# SCH_pogo-adapter-v4_2024-10-28.net
KiCad netlist of a schematic drawn in EasyEDA
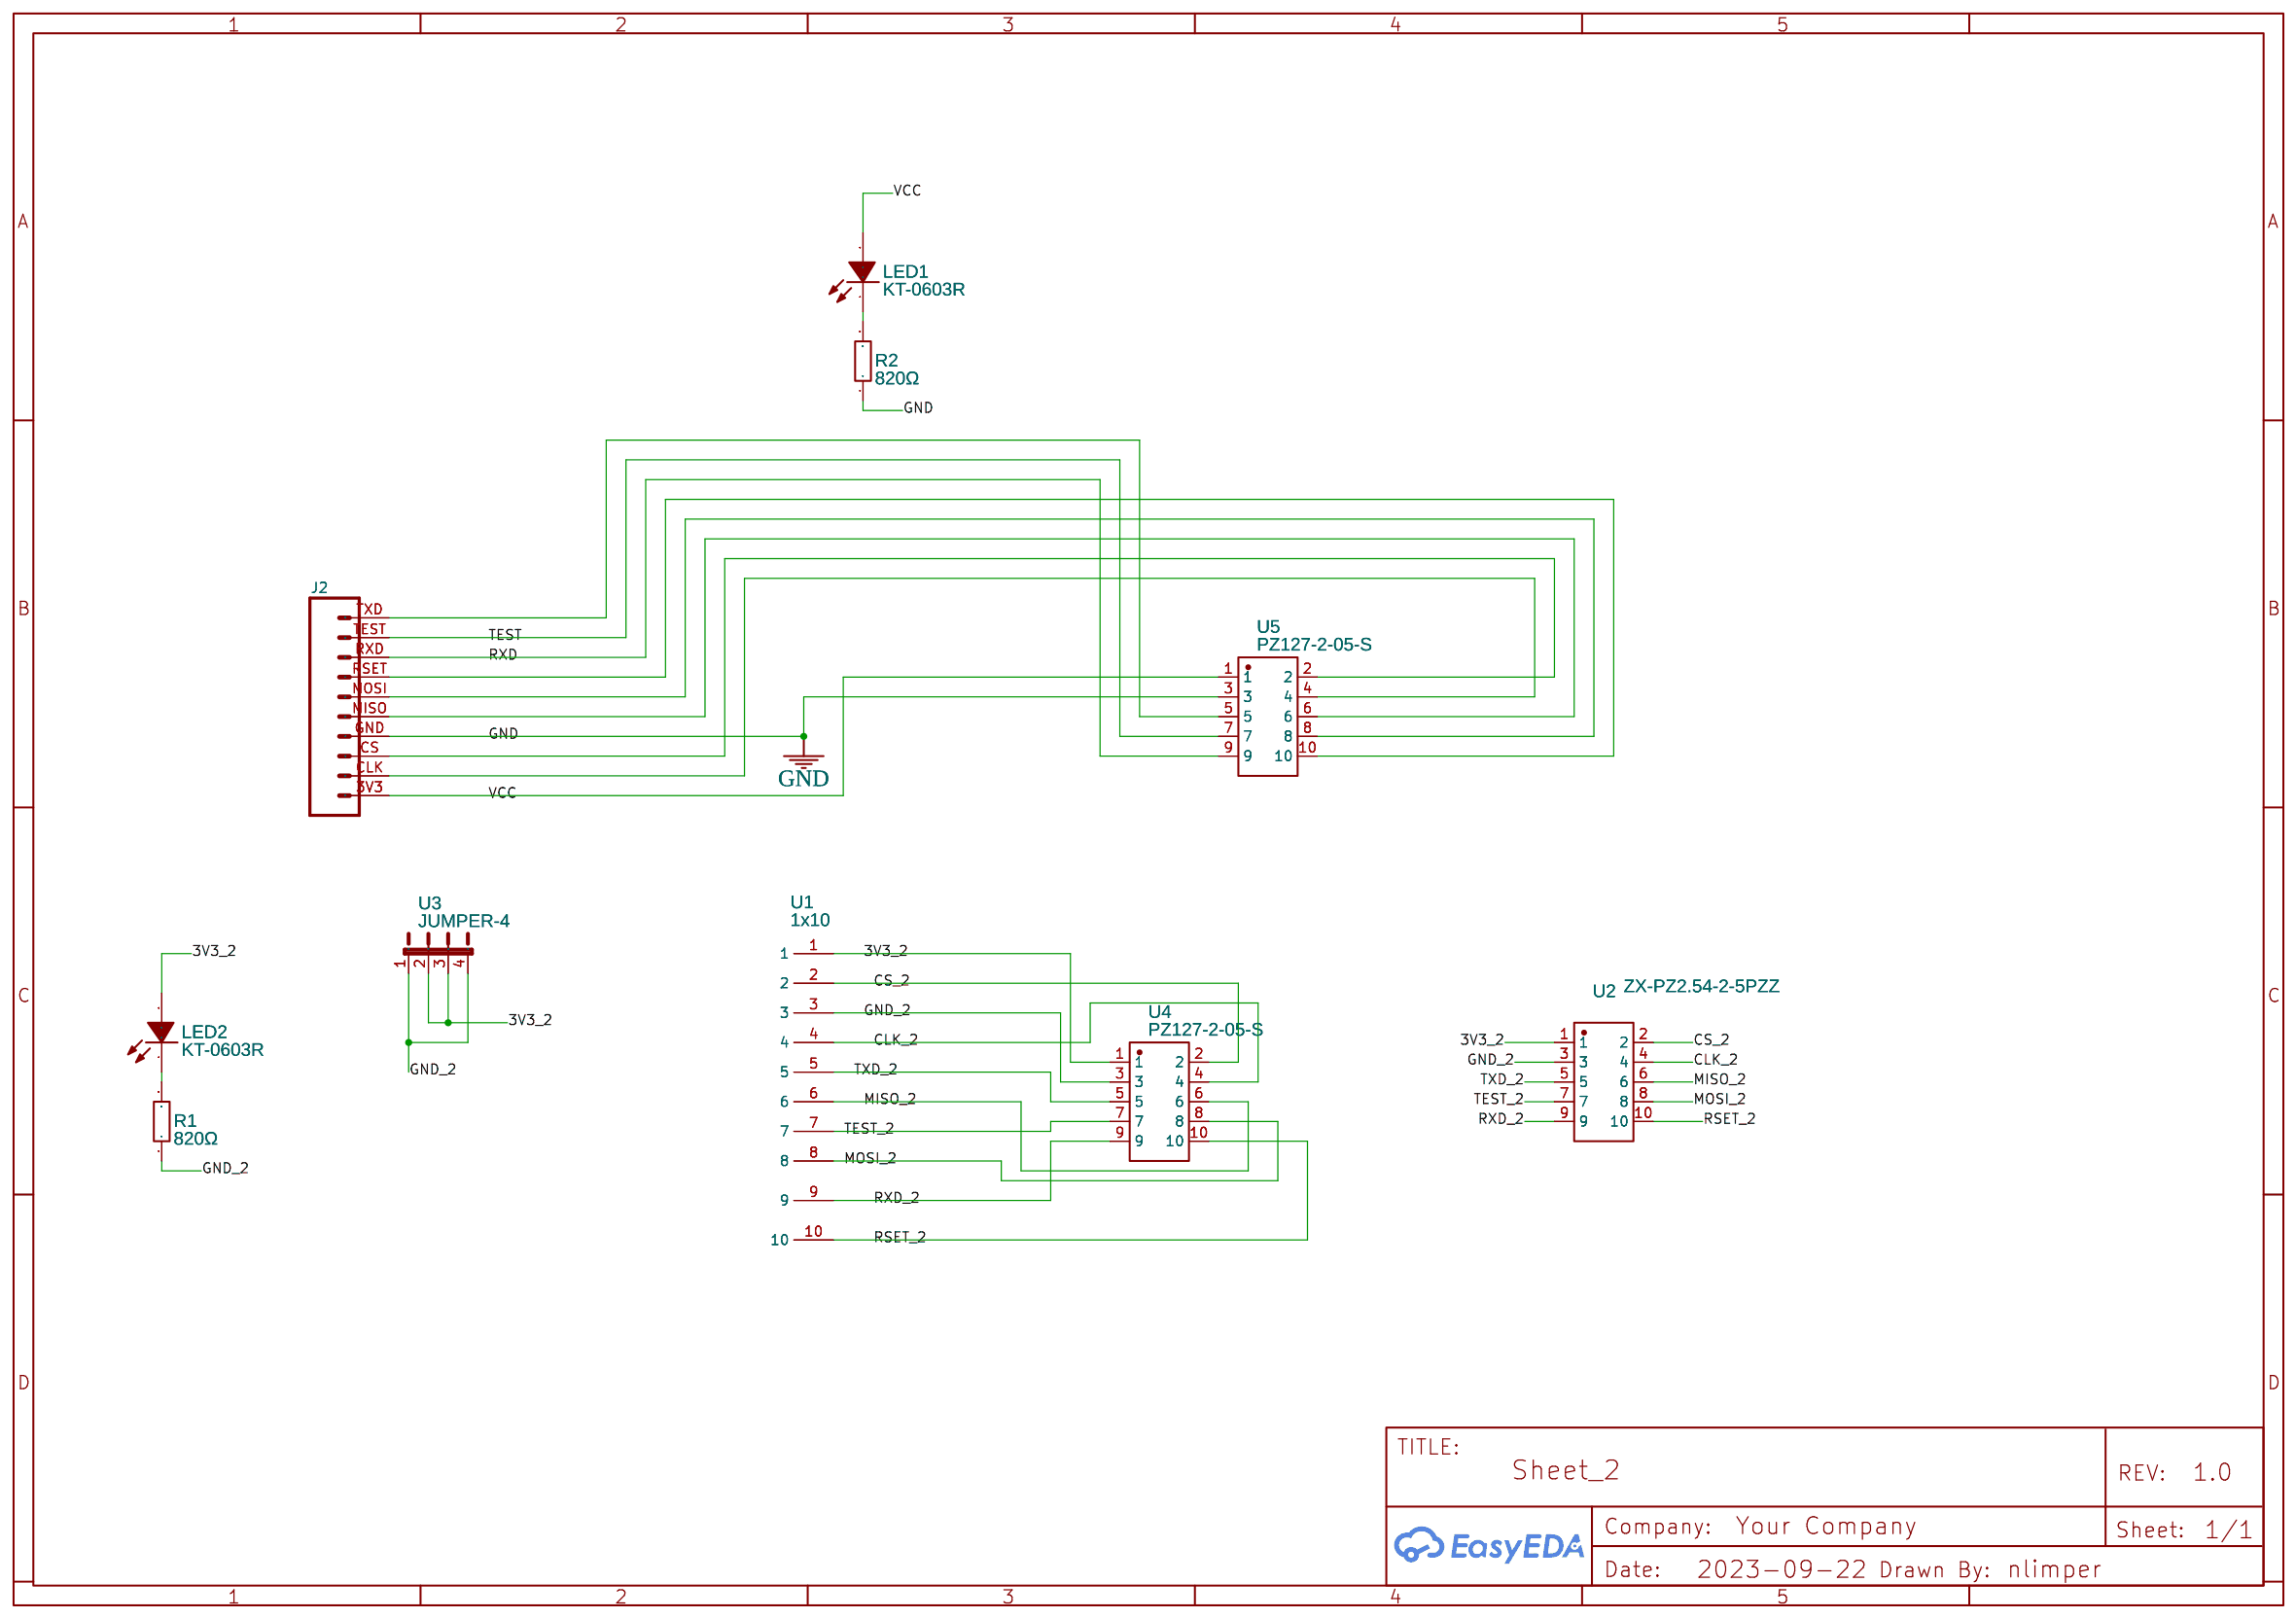
[diagram p0: schematic sheet]

(export (version "E")
  (design (tool "Eeschema 10.0.6"))
  (components
    (comp (ref "J2") (value "SOLUM_ZBS_DEBUG") (libsource (lib "") (part "Unknown_150_-480")))
    (comp (ref "LED1")
      (value "KT-0603R")
      (fields (field (name "Manufacturer") "KENTO"))
      (libsource (lib "") (part "KT-0603R"))
    )
    (comp (ref "LED2")
      (value "KT-0603R")
      (fields (field (name "Manufacturer") "KENTO"))
      (libsource (lib "") (part "KT-0603R"))
    )
    (comp (ref "R1")
      (value "820Ω")
      (fields
        (field (name "Manufacturer Part") "0402WGF8200TCE")
        (field (name "Manufacturer") "UNI-ROYAL(厚声)")
      )
      (libsource (lib "") (part "0402WGF8200TCE"))
    )
    (comp (ref "R2")
      (value "820Ω")
      (fields
        (field (name "Manufacturer Part") "0402WGF8200TCE")
        (field (name "Manufacturer") "UNI-ROYAL(厚声)")
      )
      (libsource (lib "") (part "0402WGF8200TCE"))
    )
    (comp (ref "U1") (value "1x10") (libsource (lib "") (part "1x10")))
    (comp (ref "U2")
      (value "ZX-PZ2.54-2-5PZZ")
      (fields (field (name "Manufacturer") "Megastar(兆星)"))
      (libsource (lib "") (part "ZX-PZ2.54-2-5PZZ"))
    )
    (comp (ref "U3") (value "JUMPER-4") (libsource (lib "") (part "JUMPER-4")))
    (comp (ref "U4")
      (value "PZ127-2-05-S")
      (fields (field (name "Manufacturer") "HCTL(华灿天禄)"))
      (libsource (lib "") (part "PZ127-2-05-S"))
    )
    (comp (ref "U5")
      (value "PZ127-2-05-S")
      (fields (field (name "Manufacturer") "HCTL(华灿天禄)"))
      (libsource (lib "") (part "PZ127-2-05-S"))
    )
  )
  (nets
    (net (code "1") (name "/3V3_2") (class "Default")
      (node (ref "LED2") (pin "2") (pinfunction "A_2") (pintype "unspecified"))
      (node (ref "U1") (pin "1") (pinfunction "1_1") (pintype "unspecified"))
      (node (ref "U2") (pin "1") (pinfunction "1_1") (pintype "unspecified"))
      (node (ref "U3") (pin "2") (pinfunction "2_2") (pintype "unspecified"))
      (node (ref "U3") (pin "3") (pinfunction "3_3") (pintype "unspecified"))
      (node (ref "U4") (pin "1") (pinfunction "1_1") (pintype "unspecified"))
    )
    (net (code "2") (name "/CLK_2") (class "Default")
      (node (ref "U1") (pin "4") (pinfunction "4_4") (pintype "unspecified"))
      (node (ref "U2") (pin "4") (pinfunction "4_4") (pintype "unspecified"))
      (node (ref "U4") (pin "4") (pinfunction "4_4") (pintype "unspecified"))
    )
    (net (code "3") (name "/CS_2") (class "Default")
      (node (ref "U1") (pin "2") (pinfunction "2_2") (pintype "unspecified"))
      (node (ref "U2") (pin "2") (pinfunction "2_2") (pintype "unspecified"))
      (node (ref "U4") (pin "2") (pinfunction "2_2") (pintype "unspecified"))
    )
    (net (code "4") (name "/GND_2") (class "Default")
      (node (ref "R1") (pin "1") (pinfunction "1_1") (pintype "input"))
      (node (ref "U1") (pin "3") (pinfunction "3_3") (pintype "unspecified"))
      (node (ref "U2") (pin "3") (pinfunction "3_3") (pintype "unspecified"))
      (node (ref "U3") (pin "1") (pinfunction "1_1") (pintype "unspecified"))
      (node (ref "U3") (pin "4") (pinfunction "4_4") (pintype "unspecified"))
      (node (ref "U4") (pin "3") (pinfunction "3_3") (pintype "unspecified"))
    )
    (net (code "5") (name "/MISO_2") (class "Default")
      (node (ref "U1") (pin "6") (pinfunction "6_6") (pintype "unspecified"))
      (node (ref "U2") (pin "6") (pinfunction "6_6") (pintype "unspecified"))
      (node (ref "U4") (pin "6") (pinfunction "6_6") (pintype "unspecified"))
    )
    (net (code "6") (name "/MOSI_2") (class "Default")
      (node (ref "U1") (pin "8") (pinfunction "8_8") (pintype "unspecified"))
      (node (ref "U2") (pin "8") (pinfunction "8_8") (pintype "unspecified"))
      (node (ref "U4") (pin "8") (pinfunction "8_8") (pintype "unspecified"))
    )
    (net (code "7") (name "/RSET_2") (class "Default")
      (node (ref "U1") (pin "10") (pinfunction "10_10") (pintype "unspecified"))
      (node (ref "U2") (pin "10") (pinfunction "10_10") (pintype "unspecified"))
      (node (ref "U4") (pin "10") (pinfunction "10_10") (pintype "unspecified"))
    )
    (net (code "8") (name "/RXD") (class "Default")
      (node (ref "J2") (pin "RXD") (pinfunction "8_RXD") (pintype "bidirectional"))
      (node (ref "U5") (pin "9") (pinfunction "9_9") (pintype "unspecified"))
    )
    (net (code "9") (name "/RXD_2") (class "Default")
      (node (ref "U1") (pin "9") (pinfunction "9_9") (pintype "unspecified"))
      (node (ref "U2") (pin "9") (pinfunction "9_9") (pintype "unspecified"))
      (node (ref "U4") (pin "9") (pinfunction "9_9") (pintype "unspecified"))
    )
    (net (code "10") (name "/TEST") (class "Default")
      (node (ref "J2") (pin "TEST") (pinfunction "9_TEST") (pintype "bidirectional"))
      (node (ref "U5") (pin "7") (pinfunction "7_7") (pintype "unspecified"))
    )
    (net (code "11") (name "/TEST_2") (class "Default")
      (node (ref "U1") (pin "7") (pinfunction "7_7") (pintype "unspecified"))
      (node (ref "U2") (pin "7") (pinfunction "7_7") (pintype "unspecified"))
      (node (ref "U4") (pin "7") (pinfunction "7_7") (pintype "unspecified"))
    )
    (net (code "12") (name "/TXD_2") (class "Default")
      (node (ref "U1") (pin "5") (pinfunction "5_5") (pintype "unspecified"))
      (node (ref "U2") (pin "5") (pinfunction "5_5") (pintype "unspecified"))
      (node (ref "U4") (pin "5") (pinfunction "5_5") (pintype "unspecified"))
    )
    (net (code "13") (name "/VCC") (class "Default")
      (node (ref "J2") (pin "3V3") (pinfunction "1_3V3") (pintype "bidirectional"))
      (node (ref "LED1") (pin "2") (pinfunction "A_2") (pintype "unspecified"))
      (node (ref "U5") (pin "1") (pinfunction "1_1") (pintype "unspecified"))
    )
    (net (code "14") (name "GND") (class "Default")
      (node (ref "J2") (pin "GND") (pinfunction "4_GND") (pintype "bidirectional"))
      (node (ref "R2") (pin "1") (pinfunction "1_1") (pintype "input"))
      (node (ref "U5") (pin "3") (pinfunction "3_3") (pintype "unspecified"))
    )
    (net (code "15") (name "Net-(J2-2)") (class "Default")
      (node (ref "J2") (pin "CLK") (pinfunction "2_CLK") (pintype "bidirectional"))
      (node (ref "U5") (pin "4") (pinfunction "4_4") (pintype "unspecified"))
    )
    (net (code "16") (name "Net-(J2-3)") (class "Default")
      (node (ref "J2") (pin "CS") (pinfunction "3_CS") (pintype "bidirectional"))
      (node (ref "U5") (pin "2") (pinfunction "2_2") (pintype "unspecified"))
    )
    (net (code "17") (name "Net-(J2-5)") (class "Default")
      (node (ref "J2") (pin "MISO") (pinfunction "5_MISO") (pintype "bidirectional"))
      (node (ref "U5") (pin "6") (pinfunction "6_6") (pintype "unspecified"))
    )
    (net (code "18") (name "Net-(J2-6)") (class "Default")
      (node (ref "J2") (pin "MOSI") (pinfunction "6_MOSI") (pintype "bidirectional"))
      (node (ref "U5") (pin "8") (pinfunction "8_8") (pintype "unspecified"))
    )
    (net (code "19") (name "Net-(J2-7)") (class "Default")
      (node (ref "J2") (pin "RSET") (pinfunction "7_RSET") (pintype "bidirectional"))
      (node (ref "U5") (pin "10") (pinfunction "10_10") (pintype "unspecified"))
    )
    (net (code "20") (name "Net-(J2-10)") (class "Default")
      (node (ref "J2") (pin "TXD") (pinfunction "10_TXD") (pintype "bidirectional"))
      (node (ref "U5") (pin "5") (pinfunction "5_5") (pintype "unspecified"))
    )
    (net (code "21") (name "Net-(LED1-K)") (class "Default")
      (node (ref "LED1") (pin "1") (pinfunction "K_1") (pintype "unspecified"))
      (node (ref "R2") (pin "2") (pinfunction "2_2") (pintype "input"))
    )
    (net (code "22") (name "Net-(LED2-K)") (class "Default")
      (node (ref "LED2") (pin "1") (pinfunction "K_1") (pintype "unspecified"))
      (node (ref "R1") (pin "2") (pinfunction "2_2") (pintype "input"))
    )
  )
)
